# 6ButtonTHT.net
KiCad netlist of a schematic drawn in EAGLE
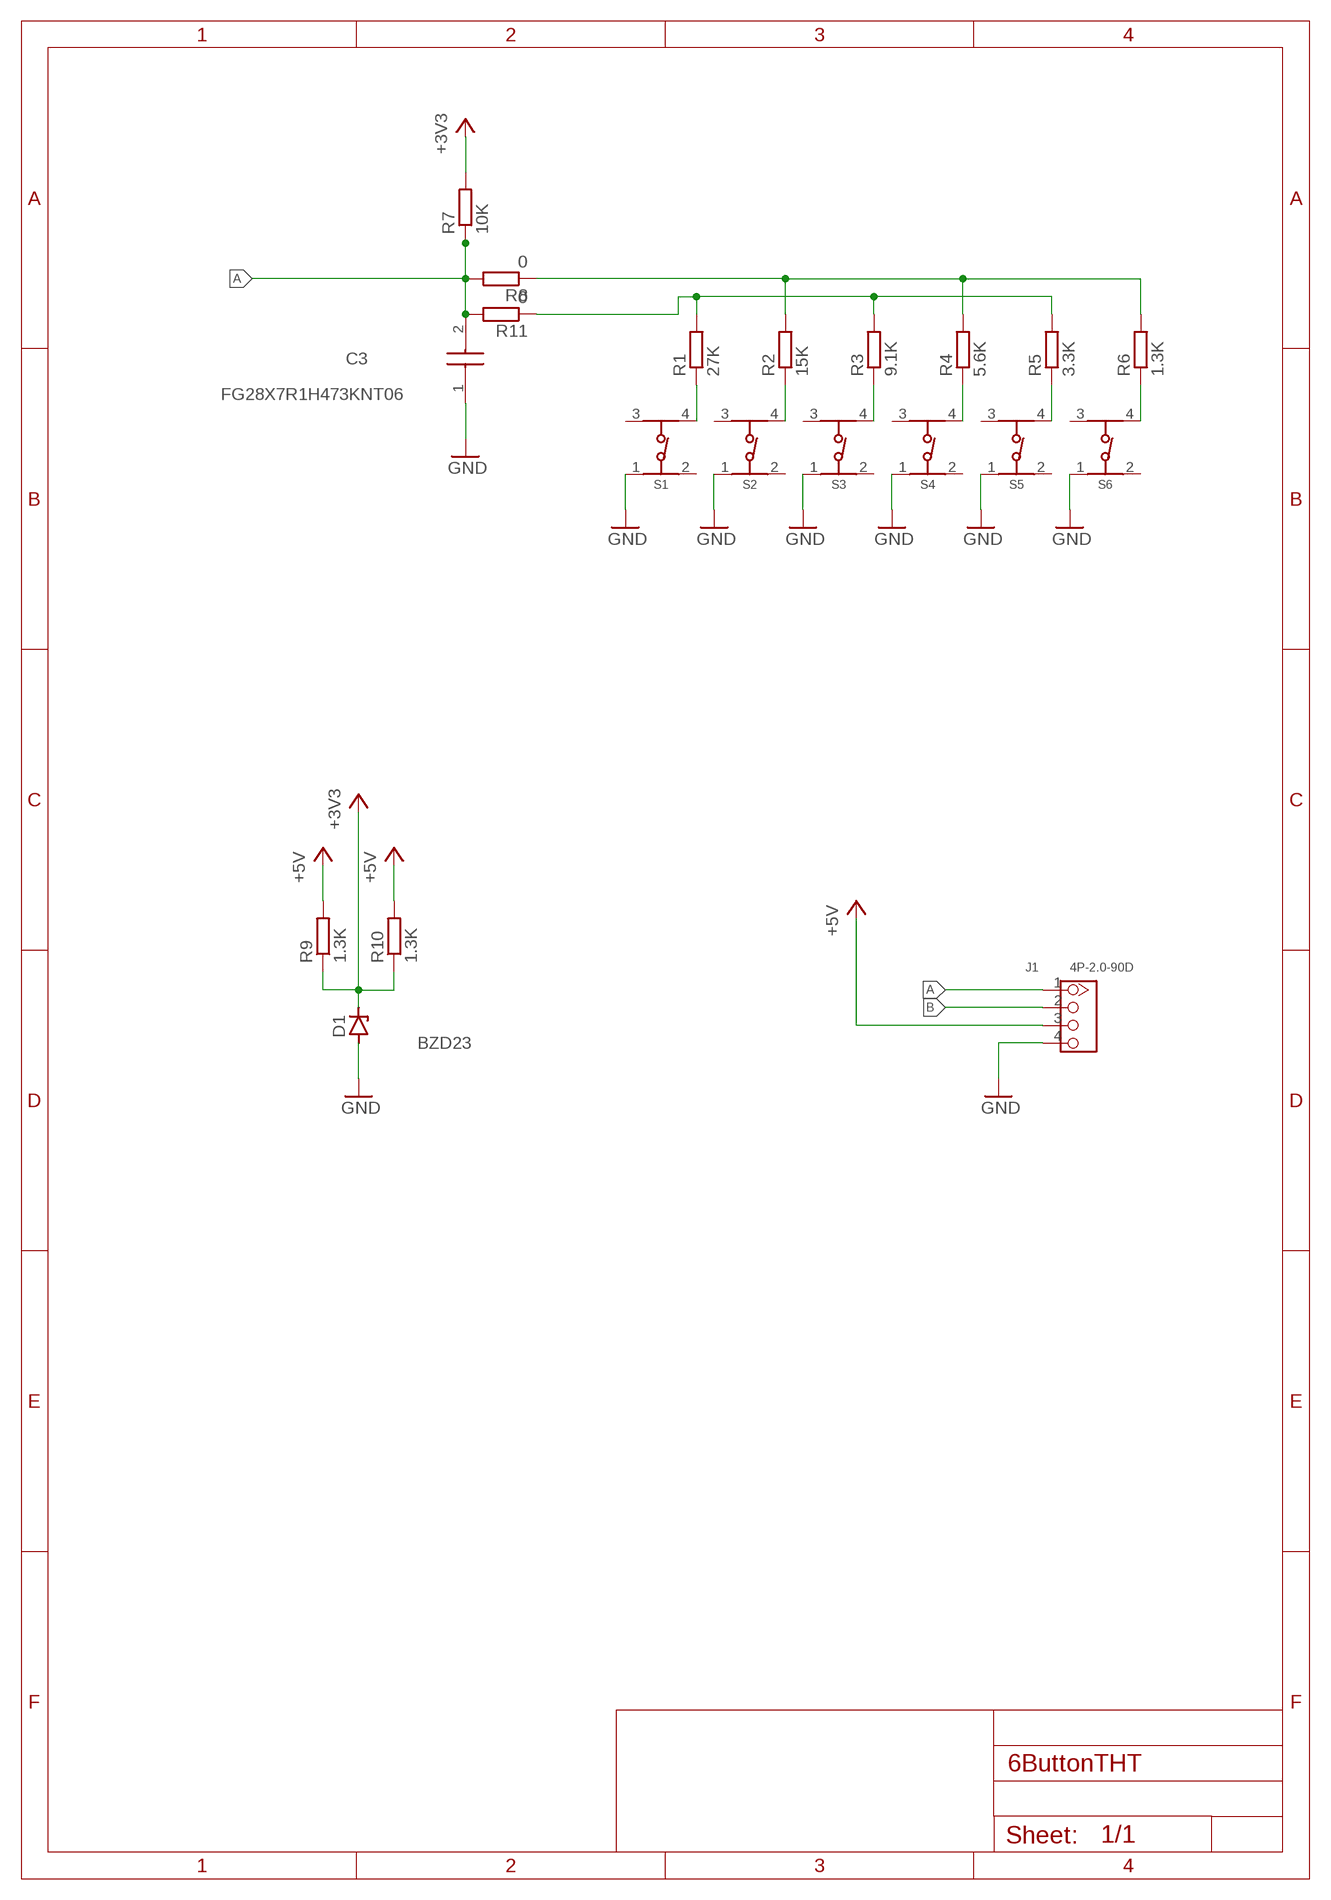
[diagram p0: schematic, sheet 1]

(export (version "E")
  (design (tool "Eeschema 10.0.6"))
  (components
    (comp (ref "C3")
      (value "FG28X7R1H473KNT06")
      (footprint "eagle-import:FG28")
      (fields (field (name "MOUSER_PART_NUMBER") "810-FG28X7R1H473KNT6"))
      (libsource (lib "eagle-import") (part "FG28X7R1H473KNT06"))
    )
    (comp (ref "D1")
      (value "BZD23")
      (footprint "eagle-import:SOD81")
      (libsource (lib "eagle-import") (part "BZD23"))
    )
    (comp (ref "J1")
      (value "4P-2.0-90D")
      (footprint "eagle-import:HW4-2.0-90D")
      (libsource (lib "eagle-import") (part "GROVE-CONNECTOR-DIP-90D(4P-2.0)"))
    )
    (comp (ref "R1")
      (value "27K")
      (footprint "eagle-import:0207_10")
      (libsource (lib "eagle-import") (part "R-EU_0207/10"))
    )
    (comp (ref "R2")
      (value "15K")
      (footprint "eagle-import:0207_10")
      (libsource (lib "eagle-import") (part "R-EU_0207/10"))
    )
    (comp (ref "R3")
      (value "9.1K")
      (footprint "eagle-import:0207_10")
      (libsource (lib "eagle-import") (part "R-EU_0207/10"))
    )
    (comp (ref "R4")
      (value "5.6K")
      (footprint "eagle-import:0207_10")
      (libsource (lib "eagle-import") (part "R-EU_0207/10"))
    )
    (comp (ref "R5")
      (value "3.3K")
      (footprint "eagle-import:0207_10")
      (libsource (lib "eagle-import") (part "R-EU_0207/10"))
    )
    (comp (ref "R6")
      (value "1.3K")
      (footprint "eagle-import:0207_10")
      (libsource (lib "eagle-import") (part "R-EU_0207/10"))
    )
    (comp (ref "R7")
      (value "10K")
      (footprint "eagle-import:0207_10")
      (libsource (lib "eagle-import") (part "R-EU_0207/10"))
    )
    (comp (ref "R8")
      (value "0")
      (footprint "eagle-import:0207_10")
      (libsource (lib "eagle-import") (part "R-EU_0207/10"))
    )
    (comp (ref "R9")
      (value "1.3K")
      (footprint "eagle-import:0207_10")
      (libsource (lib "eagle-import") (part "R-EU_0207/10"))
    )
    (comp (ref "R10")
      (value "1.3K")
      (footprint "eagle-import:0207_10")
      (libsource (lib "eagle-import") (part "R-EU_0207/10"))
    )
    (comp (ref "R11")
      (value "0")
      (footprint "eagle-import:0207_10")
      (libsource (lib "eagle-import") (part "R-EU_0207/10"))
    )
    (comp (ref "S1")
      (value "430466073726")
      (footprint "eagle-import:4304X60737X6")
      (libsource (lib "eagle-import") (part "430466073726"))
    )
    (comp (ref "S2")
      (value "430466073726")
      (footprint "eagle-import:4304X60737X6")
      (libsource (lib "eagle-import") (part "430466073726"))
    )
    (comp (ref "S3")
      (value "430466073726")
      (footprint "eagle-import:4304X60737X6")
      (libsource (lib "eagle-import") (part "430466073726"))
    )
    (comp (ref "S4")
      (value "430466073726")
      (footprint "eagle-import:4304X60737X6")
      (libsource (lib "eagle-import") (part "430466073726"))
    )
    (comp (ref "S5")
      (value "430466073726")
      (footprint "eagle-import:4304X60737X6")
      (libsource (lib "eagle-import") (part "430466073726"))
    )
    (comp (ref "S6")
      (value "430466073726")
      (footprint "eagle-import:4304X60737X6")
      (libsource (lib "eagle-import") (part "430466073726"))
    )
  )
  (nets
    (net (code "1") (name "+3V3") (class "Default")
      (node (ref "D1") (pin "C") (pinfunction "C_C") (pintype "passive"))
      (node (ref "R10") (pin "1") (pinfunction "1_1") (pintype "passive"))
      (node (ref "R7") (pin "2") (pinfunction "2_2") (pintype "passive"))
      (node (ref "R9") (pin "1") (pinfunction "1_1") (pintype "passive"))
    )
    (net (code "2") (name "+5V") (class "Default")
      (node (ref "J1") (pin "3") (pinfunction "3_3") (pintype "bidirectional"))
      (node (ref "R10") (pin "2") (pinfunction "2_2") (pintype "passive"))
      (node (ref "R9") (pin "2") (pinfunction "2_2") (pintype "passive"))
    )
    (net (code "3") (name "A") (class "Default")
      (node (ref "C3") (pin "2") (pinfunction "2_2") (pintype "bidirectional"))
      (node (ref "J1") (pin "1") (pinfunction "1_1") (pintype "bidirectional"))
      (node (ref "R11") (pin "2") (pinfunction "2_2") (pintype "passive"))
      (node (ref "R7") (pin "1") (pinfunction "1_1") (pintype "passive"))
      (node (ref "R8") (pin "2") (pinfunction "2_2") (pintype "passive"))
    )
    (net (code "4") (name "B") (class "Default")
      (node (ref "J1") (pin "2") (pinfunction "2_2") (pintype "bidirectional"))
    )
    (net (code "5") (name "GND") (class "Default")
      (node (ref "C3") (pin "1") (pinfunction "1_1") (pintype "bidirectional"))
      (node (ref "D1") (pin "A") (pinfunction "A_A") (pintype "passive"))
      (node (ref "J1") (pin "4") (pinfunction "4_4") (pintype "bidirectional"))
      (node (ref "S1") (pin "1") (pinfunction "1_1") (pintype "passive"))
      (node (ref "S2") (pin "1") (pinfunction "1_1") (pintype "passive"))
      (node (ref "S3") (pin "1") (pinfunction "1_1") (pintype "passive"))
      (node (ref "S4") (pin "1") (pinfunction "1_1") (pintype "passive"))
      (node (ref "S5") (pin "1") (pinfunction "1_1") (pintype "passive"))
      (node (ref "S6") (pin "1") (pinfunction "1_1") (pintype "passive"))
    )
    (net (code "6") (name "Net-(R1-Pad1)") (class "Default")
      (node (ref "R1") (pin "1") (pinfunction "1_1") (pintype "passive"))
      (node (ref "S1") (pin "4") (pinfunction "4_4") (pintype "passive"))
    )
    (net (code "7") (name "Net-(R1-Pad2)") (class "Default")
      (node (ref "R1") (pin "2") (pinfunction "2_2") (pintype "passive"))
      (node (ref "R11") (pin "1") (pinfunction "1_1") (pintype "passive"))
      (node (ref "R3") (pin "2") (pinfunction "2_2") (pintype "passive"))
      (node (ref "R5") (pin "2") (pinfunction "2_2") (pintype "passive"))
    )
    (net (code "8") (name "Net-(R2-Pad1)") (class "Default")
      (node (ref "R2") (pin "1") (pinfunction "1_1") (pintype "passive"))
      (node (ref "S2") (pin "4") (pinfunction "4_4") (pintype "passive"))
    )
    (net (code "9") (name "Net-(R2-Pad2)") (class "Default")
      (node (ref "R2") (pin "2") (pinfunction "2_2") (pintype "passive"))
      (node (ref "R4") (pin "2") (pinfunction "2_2") (pintype "passive"))
      (node (ref "R6") (pin "2") (pinfunction "2_2") (pintype "passive"))
      (node (ref "R8") (pin "1") (pinfunction "1_1") (pintype "passive"))
    )
    (net (code "10") (name "Net-(R3-Pad1)") (class "Default")
      (node (ref "R3") (pin "1") (pinfunction "1_1") (pintype "passive"))
      (node (ref "S3") (pin "4") (pinfunction "4_4") (pintype "passive"))
    )
    (net (code "11") (name "Net-(R4-Pad1)") (class "Default")
      (node (ref "R4") (pin "1") (pinfunction "1_1") (pintype "passive"))
      (node (ref "S4") (pin "4") (pinfunction "4_4") (pintype "passive"))
    )
    (net (code "12") (name "Net-(R5-Pad1)") (class "Default")
      (node (ref "R5") (pin "1") (pinfunction "1_1") (pintype "passive"))
      (node (ref "S5") (pin "4") (pinfunction "4_4") (pintype "passive"))
    )
    (net (code "13") (name "Net-(R6-Pad1)") (class "Default")
      (node (ref "R6") (pin "1") (pinfunction "1_1") (pintype "passive"))
      (node (ref "S6") (pin "4") (pinfunction "4_4") (pintype "passive"))
    )
    (net (code "14") (name "unconnected-(S1-2-Pad3)") (class "Default")
      (node (ref "S1") (pin "3") (pinfunction "2_3") (pintype "passive"))
    )
    (net (code "15") (name "unconnected-(S1-3-Pad2)") (class "Default")
      (node (ref "S1") (pin "2") (pinfunction "3_2") (pintype "passive"))
    )
    (net (code "16") (name "unconnected-(S2-2-Pad3)") (class "Default")
      (node (ref "S2") (pin "3") (pinfunction "2_3") (pintype "passive"))
    )
    (net (code "17") (name "unconnected-(S2-3-Pad2)") (class "Default")
      (node (ref "S2") (pin "2") (pinfunction "3_2") (pintype "passive"))
    )
    (net (code "18") (name "unconnected-(S3-2-Pad3)") (class "Default")
      (node (ref "S3") (pin "3") (pinfunction "2_3") (pintype "passive"))
    )
    (net (code "19") (name "unconnected-(S3-3-Pad2)") (class "Default")
      (node (ref "S3") (pin "2") (pinfunction "3_2") (pintype "passive"))
    )
    (net (code "20") (name "unconnected-(S4-2-Pad3)") (class "Default")
      (node (ref "S4") (pin "3") (pinfunction "2_3") (pintype "passive"))
    )
    (net (code "21") (name "unconnected-(S4-3-Pad2)") (class "Default")
      (node (ref "S4") (pin "2") (pinfunction "3_2") (pintype "passive"))
    )
    (net (code "22") (name "unconnected-(S5-2-Pad3)") (class "Default")
      (node (ref "S5") (pin "3") (pinfunction "2_3") (pintype "passive"))
    )
    (net (code "23") (name "unconnected-(S5-3-Pad2)") (class "Default")
      (node (ref "S5") (pin "2") (pinfunction "3_2") (pintype "passive"))
    )
    (net (code "24") (name "unconnected-(S6-2-Pad3)") (class "Default")
      (node (ref "S6") (pin "3") (pinfunction "2_3") (pintype "passive"))
    )
    (net (code "25") (name "unconnected-(S6-3-Pad2)") (class "Default")
      (node (ref "S6") (pin "2") (pinfunction "3_2") (pintype "passive"))
    )
  )
)
